# rgb_fb.net
KiCad netlist of a schematic drawn in EAGLE
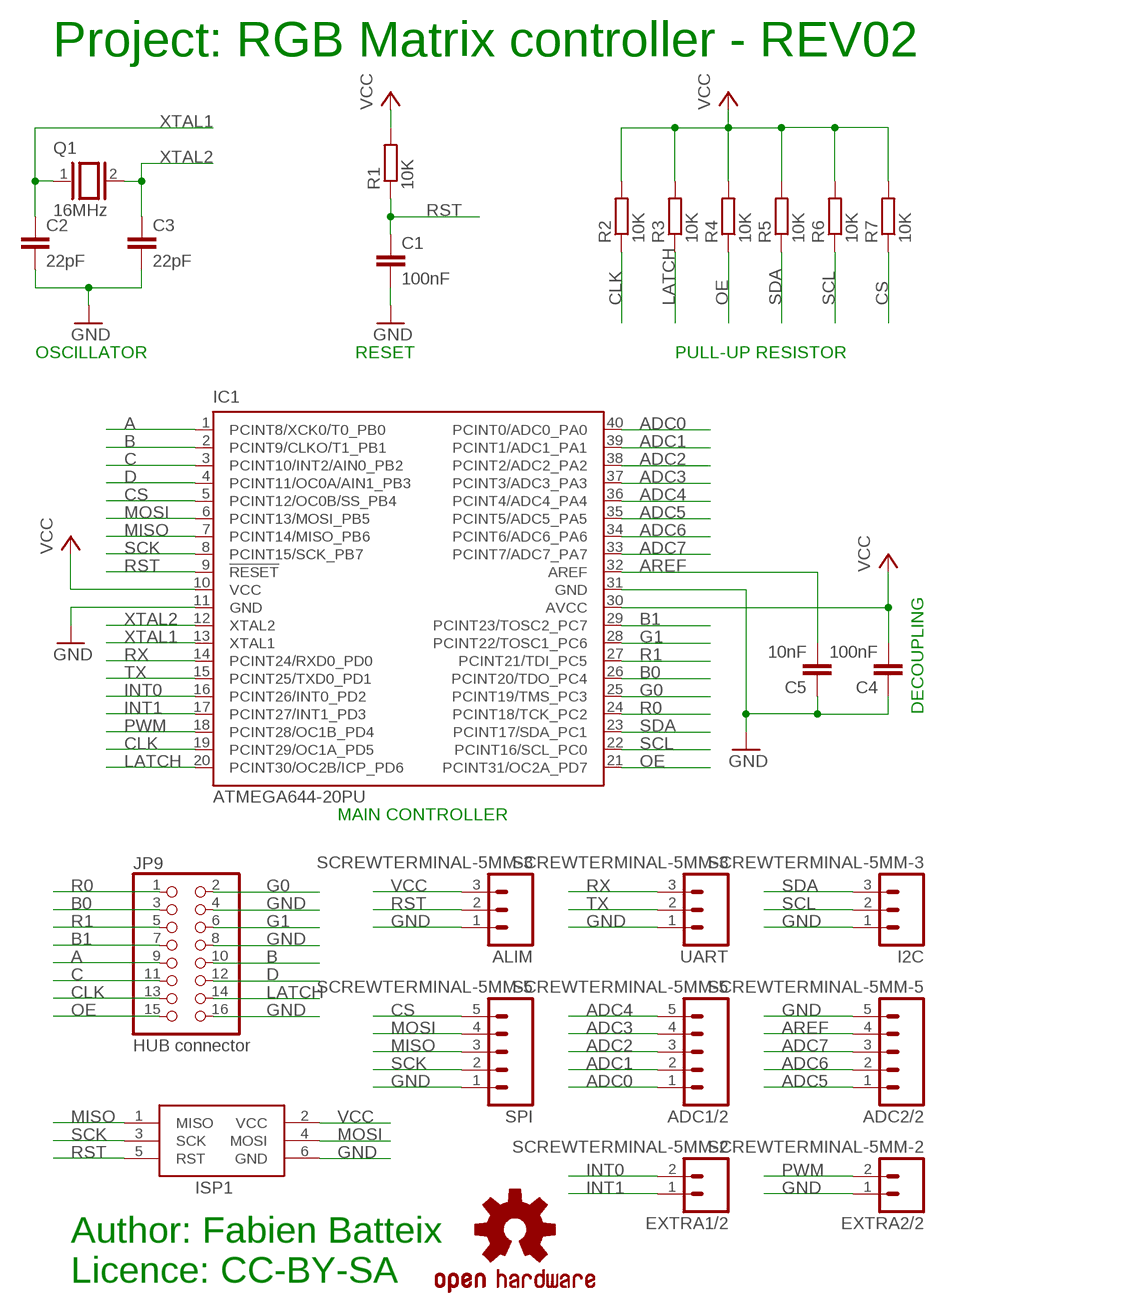
[diagram p0: schematic, sheet 1]

(export (version "E")
  (design (tool "Eeschema 10.0.6"))
  (components
    (comp (ref "ADC1/2")
      (value "SCREWTERMINAL-5MM-5")
      (footprint "eagle-import:SCREWTERMINAL-5MM-5")
      (libsource (lib "eagle-import") (part "SCREWTERMINAL-5MM-5"))
    )
    (comp (ref "ADC2/2")
      (value "SCREWTERMINAL-5MM-5")
      (footprint "eagle-import:SCREWTERMINAL-5MM-5")
      (libsource (lib "eagle-import") (part "SCREWTERMINAL-5MM-5"))
    )
    (comp (ref "ALIM")
      (value "SCREWTERMINAL-5MM-3")
      (footprint "eagle-import:SCREWTERMINAL-5MM-3")
      (libsource (lib "eagle-import") (part "SCREWTERMINAL-5MM-3"))
    )
    (comp (ref "C1")
      (value "100nF")
      (footprint "eagle-import:C5B3.5")
      (libsource (lib "eagle-import") (part "C5/3.5"))
    )
    (comp (ref "C2")
      (value "22pF")
      (footprint "eagle-import:C5B3.5")
      (libsource (lib "eagle-import") (part "C5/3.5"))
    )
    (comp (ref "C3")
      (value "22pF")
      (footprint "eagle-import:C5B3.5")
      (libsource (lib "eagle-import") (part "C5/3.5"))
    )
    (comp (ref "C4")
      (value "100nF")
      (footprint "eagle-import:C5B3.5")
      (libsource (lib "eagle-import") (part "C5/3.5"))
    )
    (comp (ref "C5")
      (value "10nF")
      (footprint "eagle-import:C5B3.5")
      (libsource (lib "eagle-import") (part "C5/3.5"))
    )
    (comp (ref "EXTRA1/2")
      (value "SCREWTERMINAL-5MM-2")
      (footprint "eagle-import:SCREWTERMINAL-5MM-2")
      (libsource (lib "eagle-import") (part "SCREWTERMINAL-5MM-2"))
    )
    (comp (ref "EXTRA2/2")
      (value "SCREWTERMINAL-5MM-2")
      (footprint "eagle-import:SCREWTERMINAL-5MM-2")
      (libsource (lib "eagle-import") (part "SCREWTERMINAL-5MM-2"))
    )
    (comp (ref "I2C")
      (value "SCREWTERMINAL-5MM-3")
      (footprint "eagle-import:SCREWTERMINAL-5MM-3")
      (libsource (lib "eagle-import") (part "SCREWTERMINAL-5MM-3"))
    )
    (comp (ref "IC1")
      (value "ATMEGA644-20PU")
      (footprint "eagle-import:DIL40")
      (libsource (lib "eagle-import") (part "ATMEGA644-PU20"))
    )
    (comp (ref "ISP1")
      (value "AVRISP-6")
      (footprint "eagle-import:AVRISP")
      (libsource (lib "eagle-import") (part "AVRISP-6"))
    )
    (comp (ref "JP9")
      (value "HUB connector")
      (footprint "eagle-import:2X08")
      (libsource (lib "eagle-import") (part "PINHD-2X8"))
    )
    (comp (ref "LOGO2")
      (value "OSHW-LOGOL")
      (footprint "eagle-import:OSHW-LOGO-L")
      (libsource (lib "eagle-import") (part "OSHW-LOGOL"))
    )
    (comp (ref "Q1")
      (value "16MHz")
      (footprint "eagle-import:QS")
      (libsource (lib "eagle-import") (part "XTAL/S"))
    )
    (comp (ref "R1")
      (value "10K")
      (footprint "eagle-import:0207_10")
      (libsource (lib "eagle-import") (part "R-EU_0207/10"))
    )
    (comp (ref "R2")
      (value "10K")
      (footprint "eagle-import:0207_10")
      (libsource (lib "eagle-import") (part "R-EU_0207/10"))
    )
    (comp (ref "R3")
      (value "10K")
      (footprint "eagle-import:0207_10")
      (libsource (lib "eagle-import") (part "R-EU_0207/10"))
    )
    (comp (ref "R4")
      (value "10K")
      (footprint "eagle-import:0207_10")
      (libsource (lib "eagle-import") (part "R-EU_0207/10"))
    )
    (comp (ref "R5")
      (value "10K")
      (footprint "eagle-import:0207_10")
      (libsource (lib "eagle-import") (part "R-EU_0207/10"))
    )
    (comp (ref "R6")
      (value "10K")
      (footprint "eagle-import:0207_10")
      (libsource (lib "eagle-import") (part "R-EU_0207/10"))
    )
    (comp (ref "R7")
      (value "10K")
      (footprint "eagle-import:0207_10")
      (libsource (lib "eagle-import") (part "R-EU_0207/10"))
    )
    (comp (ref "SPI")
      (value "SCREWTERMINAL-5MM-5")
      (footprint "eagle-import:SCREWTERMINAL-5MM-5")
      (libsource (lib "eagle-import") (part "SCREWTERMINAL-5MM-5"))
    )
    (comp (ref "UART")
      (value "SCREWTERMINAL-5MM-3")
      (footprint "eagle-import:SCREWTERMINAL-5MM-3")
      (libsource (lib "eagle-import") (part "SCREWTERMINAL-5MM-3"))
    )
  )
  (nets
    (net (code "1") (name "/A") (class "Default")
      (node (ref "IC1") (pin "1") (pinfunction "PCINT8/XCK0/T0_PB0_1") (pintype "bidirectional"))
      (node (ref "JP9") (pin "9") (pinfunction "9_9") (pintype "passive"))
    )
    (net (code "2") (name "/ADC0") (class "Default")
      (node (ref "ADC1/2") (pin "1") (pinfunction "1_1") (pintype "passive"))
      (node (ref "IC1") (pin "40") (pinfunction "PCINT0/ADC0_PA0_40") (pintype "bidirectional"))
    )
    (net (code "3") (name "/ADC1") (class "Default")
      (node (ref "ADC1/2") (pin "2") (pinfunction "2_2") (pintype "passive"))
      (node (ref "IC1") (pin "39") (pinfunction "PCINT1/ADC1_PA1_39") (pintype "bidirectional"))
    )
    (net (code "4") (name "/ADC2") (class "Default")
      (node (ref "ADC1/2") (pin "3") (pinfunction "3_3") (pintype "passive"))
      (node (ref "IC1") (pin "38") (pinfunction "PCINT2/ADC2_PA2_38") (pintype "bidirectional"))
    )
    (net (code "5") (name "/ADC3") (class "Default")
      (node (ref "ADC1/2") (pin "4") (pinfunction "4_4") (pintype "passive"))
      (node (ref "IC1") (pin "37") (pinfunction "PCINT3/ADC3_PA3_37") (pintype "bidirectional"))
    )
    (net (code "6") (name "/ADC4") (class "Default")
      (node (ref "ADC1/2") (pin "5") (pinfunction "5_5") (pintype "passive"))
      (node (ref "IC1") (pin "36") (pinfunction "PCINT4/ADC4_PA4_36") (pintype "bidirectional"))
    )
    (net (code "7") (name "/ADC5") (class "Default")
      (node (ref "ADC2/2") (pin "1") (pinfunction "1_1") (pintype "passive"))
      (node (ref "IC1") (pin "35") (pinfunction "PCINT5/ADC5_PA5_35") (pintype "bidirectional"))
    )
    (net (code "8") (name "/ADC6") (class "Default")
      (node (ref "ADC2/2") (pin "2") (pinfunction "2_2") (pintype "passive"))
      (node (ref "IC1") (pin "34") (pinfunction "PCINT6/ADC6_PA6_34") (pintype "bidirectional"))
    )
    (net (code "9") (name "/ADC7") (class "Default")
      (node (ref "ADC2/2") (pin "3") (pinfunction "3_3") (pintype "passive"))
      (node (ref "IC1") (pin "33") (pinfunction "PCINT7/ADC7_PA7_33") (pintype "bidirectional"))
    )
    (net (code "10") (name "/AREF") (class "Default")
      (node (ref "ADC2/2") (pin "4") (pinfunction "4_4") (pintype "passive"))
      (node (ref "C5") (pin "2") (pinfunction "2_2") (pintype "passive"))
      (node (ref "IC1") (pin "32") (pinfunction "AREF_32") (pintype "passive"))
    )
    (net (code "11") (name "/B") (class "Default")
      (node (ref "IC1") (pin "2") (pinfunction "PCINT9/CLKO/T1_PB1_2") (pintype "bidirectional"))
      (node (ref "JP9") (pin "10") (pinfunction "10_10") (pintype "passive"))
    )
    (net (code "12") (name "/B0") (class "Default")
      (node (ref "IC1") (pin "26") (pinfunction "PCINT20/TDO_PC4_26") (pintype "bidirectional"))
      (node (ref "JP9") (pin "3") (pinfunction "3_3") (pintype "passive"))
    )
    (net (code "13") (name "/B1") (class "Default")
      (node (ref "IC1") (pin "29") (pinfunction "PCINT23/TOSC2_PC7_29") (pintype "bidirectional"))
      (node (ref "JP9") (pin "7") (pinfunction "7_7") (pintype "passive"))
    )
    (net (code "14") (name "/C") (class "Default")
      (node (ref "IC1") (pin "3") (pinfunction "PCINT10/INT2/AIN0_PB2_3") (pintype "bidirectional"))
      (node (ref "JP9") (pin "11") (pinfunction "11_11") (pintype "passive"))
    )
    (net (code "15") (name "/CLK") (class "Default")
      (node (ref "IC1") (pin "19") (pinfunction "PCINT29/OC1A_PD5_19") (pintype "bidirectional"))
      (node (ref "JP9") (pin "13") (pinfunction "13_13") (pintype "passive"))
      (node (ref "R2") (pin "1") (pinfunction "1_1") (pintype "passive"))
    )
    (net (code "16") (name "/CS") (class "Default")
      (node (ref "IC1") (pin "5") (pinfunction "PCINT12/OC0B/SS_PB4_5") (pintype "bidirectional"))
      (node (ref "R7") (pin "1") (pinfunction "1_1") (pintype "passive"))
      (node (ref "SPI") (pin "5") (pinfunction "5_5") (pintype "passive"))
    )
    (net (code "17") (name "/D") (class "Default")
      (node (ref "IC1") (pin "4") (pinfunction "PCINT11/OC0A/AIN1_PB3_4") (pintype "bidirectional"))
      (node (ref "JP9") (pin "12") (pinfunction "12_12") (pintype "passive"))
    )
    (net (code "18") (name "/G0") (class "Default")
      (node (ref "IC1") (pin "25") (pinfunction "PCINT19/TMS_PC3_25") (pintype "bidirectional"))
      (node (ref "JP9") (pin "2") (pinfunction "2_2") (pintype "passive"))
    )
    (net (code "19") (name "/G1") (class "Default")
      (node (ref "IC1") (pin "28") (pinfunction "PCINT22/TOSC1_PC6_28") (pintype "bidirectional"))
      (node (ref "JP9") (pin "6") (pinfunction "6_6") (pintype "passive"))
    )
    (net (code "20") (name "/INT0") (class "Default")
      (node (ref "EXTRA1/2") (pin "2") (pinfunction "2_2") (pintype "passive"))
      (node (ref "IC1") (pin "16") (pinfunction "PCINT26/INT0_PD2_16") (pintype "bidirectional"))
    )
    (net (code "21") (name "/INT1") (class "Default")
      (node (ref "EXTRA1/2") (pin "1") (pinfunction "1_1") (pintype "passive"))
      (node (ref "IC1") (pin "17") (pinfunction "PCINT27/INT1_PD3_17") (pintype "bidirectional"))
    )
    (net (code "22") (name "/LATCH") (class "Default")
      (node (ref "IC1") (pin "20") (pinfunction "PCINT30/OC2B/ICP_PD6_20") (pintype "bidirectional"))
      (node (ref "JP9") (pin "14") (pinfunction "14_14") (pintype "passive"))
      (node (ref "R3") (pin "1") (pinfunction "1_1") (pintype "passive"))
    )
    (net (code "23") (name "/MISO") (class "Default")
      (node (ref "IC1") (pin "7") (pinfunction "PCINT14/MISO_PB6_7") (pintype "bidirectional"))
      (node (ref "ISP1") (pin "1") (pinfunction "MISO_1") (pintype "input"))
      (node (ref "SPI") (pin "3") (pinfunction "3_3") (pintype "passive"))
    )
    (net (code "24") (name "/MOSI") (class "Default")
      (node (ref "IC1") (pin "6") (pinfunction "PCINT13/MOSI_PB5_6") (pintype "bidirectional"))
      (node (ref "ISP1") (pin "4") (pinfunction "MOSI_4") (pintype "output"))
      (node (ref "SPI") (pin "4") (pinfunction "4_4") (pintype "passive"))
    )
    (net (code "25") (name "/OE") (class "Default")
      (node (ref "IC1") (pin "21") (pinfunction "PCINT31/OC2A_PD7_21") (pintype "bidirectional"))
      (node (ref "JP9") (pin "15") (pinfunction "15_15") (pintype "passive"))
      (node (ref "R4") (pin "1") (pinfunction "1_1") (pintype "passive"))
    )
    (net (code "26") (name "/PWM") (class "Default")
      (node (ref "EXTRA2/2") (pin "2") (pinfunction "2_2") (pintype "passive"))
      (node (ref "IC1") (pin "18") (pinfunction "PCINT28/OC1B_PD4_18") (pintype "bidirectional"))
    )
    (net (code "27") (name "/R0") (class "Default")
      (node (ref "IC1") (pin "24") (pinfunction "PCINT18/TCK_PC2_24") (pintype "bidirectional"))
      (node (ref "JP9") (pin "1") (pinfunction "1_1") (pintype "passive"))
    )
    (net (code "28") (name "/R1") (class "Default")
      (node (ref "IC1") (pin "27") (pinfunction "PCINT21/TDI_PC5_27") (pintype "bidirectional"))
      (node (ref "JP9") (pin "5") (pinfunction "5_5") (pintype "passive"))
    )
    (net (code "29") (name "/RST") (class "Default")
      (node (ref "ALIM") (pin "2") (pinfunction "2_2") (pintype "passive"))
      (node (ref "C1") (pin "1") (pinfunction "1_1") (pintype "passive"))
      (node (ref "IC1") (pin "9") (pinfunction "~{RESET}_9") (pintype "input"))
      (node (ref "ISP1") (pin "5") (pinfunction "RST_5") (pintype "output"))
      (node (ref "R1") (pin "1") (pinfunction "1_1") (pintype "passive"))
    )
    (net (code "30") (name "/RX") (class "Default")
      (node (ref "IC1") (pin "14") (pinfunction "PCINT24/RXD0_PD0_14") (pintype "bidirectional"))
      (node (ref "UART") (pin "3") (pinfunction "3_3") (pintype "passive"))
    )
    (net (code "31") (name "/SCK") (class "Default")
      (node (ref "IC1") (pin "8") (pinfunction "PCINT15/SCK_PB7_8") (pintype "bidirectional"))
      (node (ref "ISP1") (pin "3") (pinfunction "SCK_3") (pintype "output"))
      (node (ref "SPI") (pin "2") (pinfunction "2_2") (pintype "passive"))
    )
    (net (code "32") (name "/SCL") (class "Default")
      (node (ref "I2C") (pin "2") (pinfunction "2_2") (pintype "passive"))
      (node (ref "IC1") (pin "22") (pinfunction "PCINT16/SCL_PC0_22") (pintype "bidirectional"))
      (node (ref "R6") (pin "1") (pinfunction "1_1") (pintype "passive"))
    )
    (net (code "33") (name "/SDA") (class "Default")
      (node (ref "I2C") (pin "3") (pinfunction "3_3") (pintype "passive"))
      (node (ref "IC1") (pin "23") (pinfunction "PCINT17/SDA_PC1_23") (pintype "bidirectional"))
      (node (ref "R5") (pin "1") (pinfunction "1_1") (pintype "passive"))
    )
    (net (code "34") (name "/TX") (class "Default")
      (node (ref "IC1") (pin "15") (pinfunction "PCINT25/TXD0_PD1_15") (pintype "bidirectional"))
      (node (ref "UART") (pin "2") (pinfunction "2_2") (pintype "passive"))
    )
    (net (code "35") (name "/XTAL1") (class "Default")
      (node (ref "C2") (pin "1") (pinfunction "1_1") (pintype "passive"))
      (node (ref "IC1") (pin "13") (pinfunction "XTAL1_13") (pintype "input"))
      (node (ref "Q1") (pin "1") (pinfunction "1_1") (pintype "passive"))
    )
    (net (code "36") (name "/XTAL2") (class "Default")
      (node (ref "C3") (pin "1") (pinfunction "1_1") (pintype "passive"))
      (node (ref "IC1") (pin "12") (pinfunction "XTAL2_12") (pintype "output"))
      (node (ref "Q1") (pin "2") (pinfunction "2_2") (pintype "passive"))
    )
    (net (code "37") (name "GND") (class "Default")
      (node (ref "ADC2/2") (pin "5") (pinfunction "5_5") (pintype "passive"))
      (node (ref "ALIM") (pin "1") (pinfunction "1_1") (pintype "passive"))
      (node (ref "C1") (pin "2") (pinfunction "2_2") (pintype "passive"))
      (node (ref "C2") (pin "2") (pinfunction "2_2") (pintype "passive"))
      (node (ref "C3") (pin "2") (pinfunction "2_2") (pintype "passive"))
      (node (ref "C4") (pin "1") (pinfunction "1_1") (pintype "passive"))
      (node (ref "C5") (pin "1") (pinfunction "1_1") (pintype "passive"))
      (node (ref "EXTRA2/2") (pin "1") (pinfunction "1_1") (pintype "passive"))
      (node (ref "I2C") (pin "1") (pinfunction "1_1") (pintype "passive"))
      (node (ref "IC1") (pin "11") (pinfunction "GND_11") (pintype "power_in"))
      (node (ref "IC1") (pin "31") (pinfunction "GND_31") (pintype "power_in"))
      (node (ref "ISP1") (pin "6") (pinfunction "GND_6") (pintype "power_in"))
      (node (ref "JP9") (pin "16") (pinfunction "16_16") (pintype "passive"))
      (node (ref "JP9") (pin "4") (pinfunction "4_4") (pintype "passive"))
      (node (ref "JP9") (pin "8") (pinfunction "8_8") (pintype "passive"))
      (node (ref "SPI") (pin "1") (pinfunction "1_1") (pintype "passive"))
      (node (ref "UART") (pin "1") (pinfunction "1_1") (pintype "passive"))
    )
    (net (code "38") (name "VCC") (class "Default")
      (node (ref "ALIM") (pin "3") (pinfunction "3_3") (pintype "passive"))
      (node (ref "C4") (pin "2") (pinfunction "2_2") (pintype "passive"))
      (node (ref "IC1") (pin "10") (pinfunction "VCC_10") (pintype "power_in"))
      (node (ref "IC1") (pin "30") (pinfunction "AVCC_30") (pintype "power_in"))
      (node (ref "ISP1") (pin "2") (pinfunction "VCC_2") (pintype "power_in"))
      (node (ref "R1") (pin "2") (pinfunction "2_2") (pintype "passive"))
      (node (ref "R2") (pin "2") (pinfunction "2_2") (pintype "passive"))
      (node (ref "R3") (pin "2") (pinfunction "2_2") (pintype "passive"))
      (node (ref "R4") (pin "2") (pinfunction "2_2") (pintype "passive"))
      (node (ref "R5") (pin "2") (pinfunction "2_2") (pintype "passive"))
      (node (ref "R6") (pin "2") (pinfunction "2_2") (pintype "passive"))
      (node (ref "R7") (pin "2") (pinfunction "2_2") (pintype "passive"))
    )
  )
)
